# NTC.net
KiCad netlist of a schematic drawn in Altium Designer
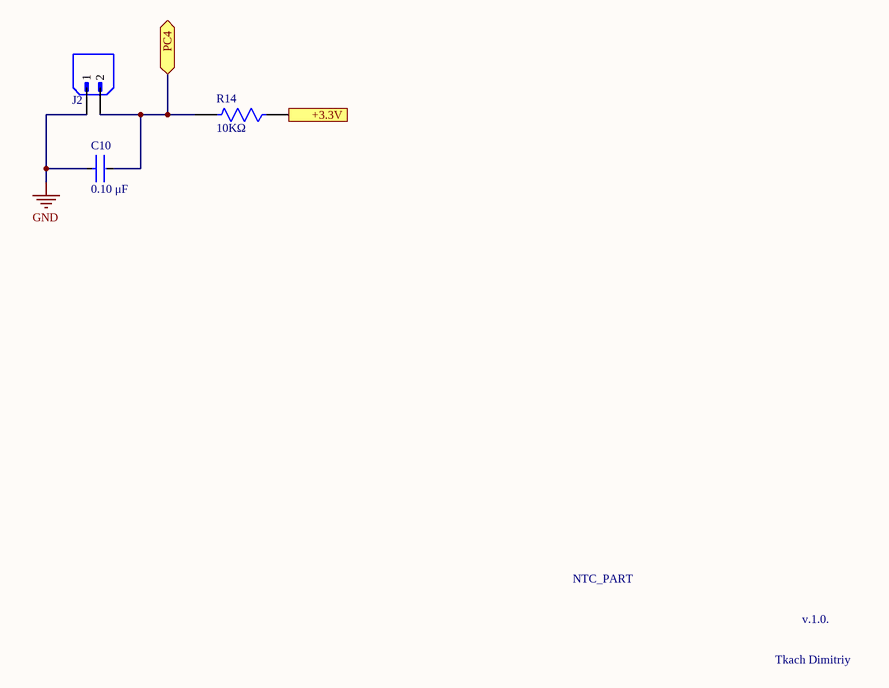
[diagram p0: NTC.SchDoc]

(export (version "E")
  (design (tool "Eeschema 10.0.6"))
  (components
    (comp (ref "C10")
      (value "C1206C104K5RACAUTO")
      (footprint "CAPC3216X18M")
      (description "CAP CER 0.1UF 50V X7R 1206")
      (fields
        (field (name "MANUFACTURER") "KEMET")
        (field (name "OCTOPART") "https://octopart.com/c1206c104k5racauto-kemet-12595586")
        (field (name "CAPACITANCE") "0.10 μF")
      )
      (libsource (lib "Internal_Lib_Thermostat_STM8") (part "CMP-03020-005759-1"))
    )
    (comp (ref "J2")
      (value "B2B-XH-A")
      (footprint "JST_B2B-XH-A")
      (fields (field (name "MF") "{'manufacturer': u'JST Sales America Inc.'}"))
      (libsource (lib "Internal_Lib_Thermostat_STM8") (part "CMP-033-000000-1"))
    )
    (comp (ref "R14")
      (value "CRGP1206F10K")
      (footprint "RESC3216X06M")
      (description "CRGP 1206 10K 1%")
      (fields
        (field (name "OCTOPART") "https://octopart.com/crgp1206f10k-te+connectivity-91018843")
        (field (name "TOLERANCE") "0.01")
        (field (name "RESISTANCE") "10KΩ")
      )
      (libsource (lib "Internal_Lib_Thermostat_STM8") (part "CMP-03211-004788-1"))
    )
  )
  (nets
    (net (code "1") (name "/+3.3V") (class "Default")
      (node (ref "R14") (pin "1") (pinfunction "1_1") (pintype "passive"))
    )
    (net (code "2") (name "/PC4") (class "Default")
      (node (ref "C10") (pin "2") (pinfunction "2_2") (pintype "passive"))
      (node (ref "J2") (pin "2") (pinfunction "2_2") (pintype "passive"))
      (node (ref "R14") (pin "2") (pinfunction "2_2") (pintype "passive"))
    )
    (net (code "3") (name "GND") (class "Default")
      (node (ref "C10") (pin "1") (pinfunction "1_1") (pintype "passive"))
      (node (ref "J2") (pin "1") (pinfunction "1_1") (pintype "passive"))
    )
  )
)
